# GPS.net
KiCad netlist of a schematic drawn in EAGLE
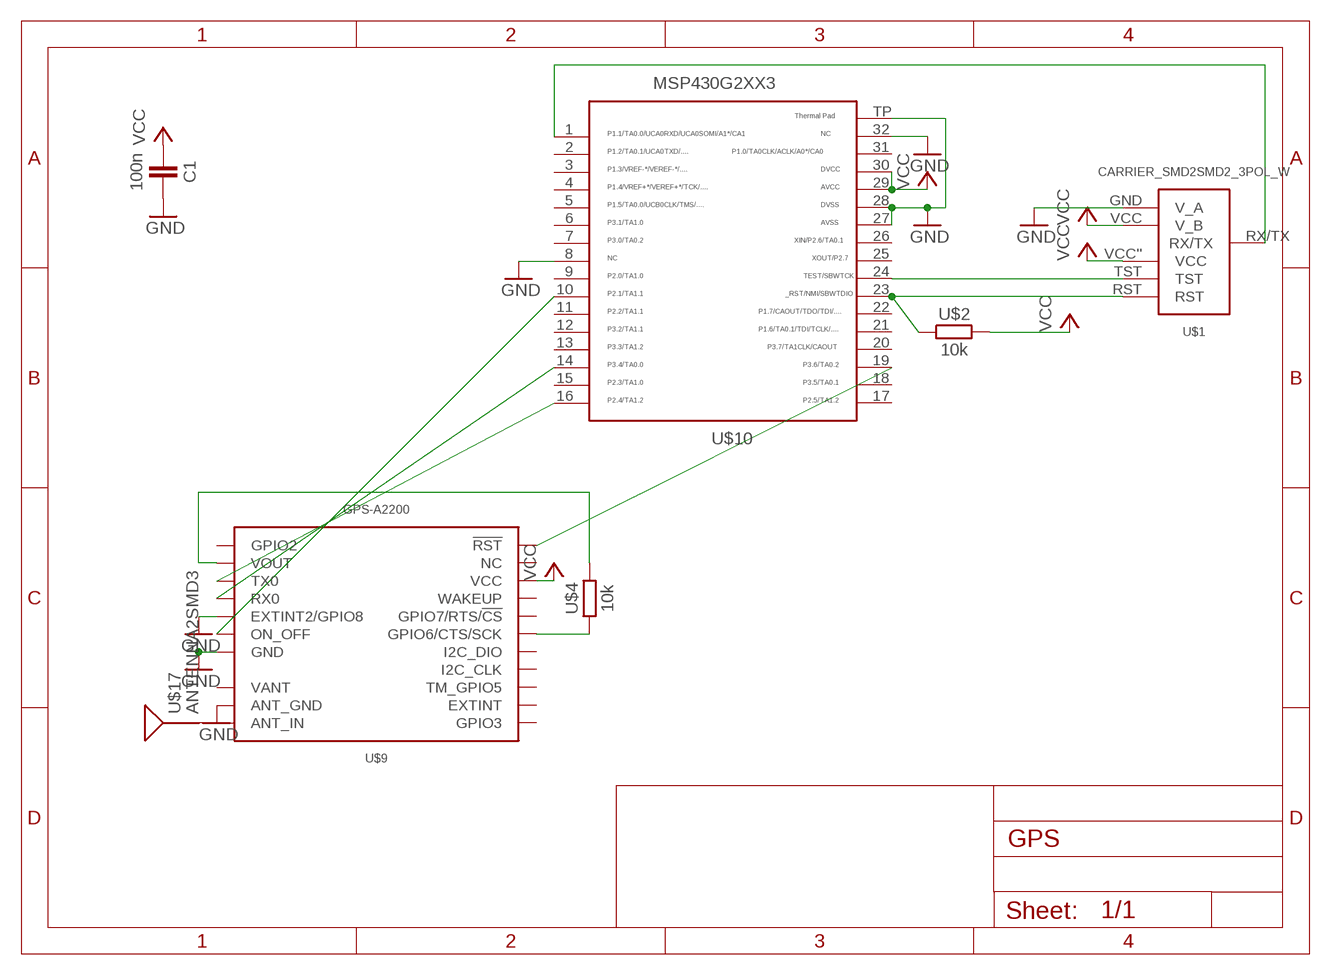
[diagram p0: schematic, sheet 1]

(export (version "E")
  (design (tool "Eeschema 10.0.6"))
  (components
    (comp (ref "C1")
      (value "100n")
      (footprint "eagle-import:603")
      (libsource (lib "eagle-import") (part "CAPACITOR"))
    )
    (comp (ref "U$1")
      (value "CARRIER_SMD2SMD2_3POL_W")
      (footprint "eagle-import:CARRIER_SMD2_WIDE_3POL")
      (libsource (lib "eagle-import") (part "CARRIER_SMD2SMD2_3POL_W"))
    )
    (comp (ref "U$2")
      (value "10k")
      (footprint "eagle-import:603")
      (libsource (lib "eagle-import") (part "RESISTOR0603"))
    )
    (comp (ref "U$4")
      (value "10k")
      (footprint "eagle-import:603")
      (libsource (lib "eagle-import") (part "RESISTOR0603"))
    )
    (comp (ref "U$9")
      (value "GPS-A2200")
      (footprint "eagle-import:A2200")
      (libsource (lib "eagle-import") (part "GPS-A2200"))
    )
    (comp (ref "U$10")
      (value "MSP430G2553")
      (footprint "eagle-import:QFN32")
      (libsource (lib "eagle-import") (part "MSP430G2553"))
    )
    (comp (ref "U$17")
      (value "ANTENNA2SMD3")
      (footprint "eagle-import:ANTENNA-CHIP4")
      (libsource (lib "eagle-import") (part "ANTENNA2SMD3"))
    )
  )
  (nets
    (net (code "1") (name "GND") (class "Default")
      (node (ref "C1") (pin "2") (pinfunction "2_2") (pintype "passive"))
      (node (ref "U$1") (pin "GND") (pinfunction "V_A_GND") (pintype "bidirectional"))
      (node (ref "U$10") (pin "27") (pinfunction "27_27") (pintype "bidirectional"))
      (node (ref "U$10") (pin "28") (pinfunction "28_28") (pintype "bidirectional"))
      (node (ref "U$10") (pin "32") (pinfunction "32_32") (pintype "bidirectional"))
      (node (ref "U$10") (pin "8") (pinfunction "8_8") (pintype "bidirectional"))
      (node (ref "U$10") (pin "TP") (pinfunction "TP_TP") (pintype "bidirectional"))
      (node (ref "U$9") (pin "ANT_GND") (pinfunction "ANT_GND_ANT_GND") (pintype "power_in"))
      (node (ref "U$9") (pin "EXTINT2/GPIO8") (pinfunction "EXTINT2/GPIO8_EXTINT2/GPIO8") (pintype "bidirectional"))
      (node (ref "U$9") (pin "GND@1") (pinfunction "GND_GND@1") (pintype "power_in"))
      (node (ref "U$9") (pin "GND@10") (pinfunction "GND_GND@10") (pintype "power_in"))
      (node (ref "U$9") (pin "GND@11") (pinfunction "GND_GND@11") (pintype "power_in"))
      (node (ref "U$9") (pin "GND@2") (pinfunction "GND_GND@2") (pintype "power_in"))
      (node (ref "U$9") (pin "GND@3") (pinfunction "GND_GND@3") (pintype "power_in"))
      (node (ref "U$9") (pin "GND@4") (pinfunction "GND_GND@4") (pintype "power_in"))
      (node (ref "U$9") (pin "GND@5") (pinfunction "GND_GND@5") (pintype "power_in"))
      (node (ref "U$9") (pin "GND@6") (pinfunction "GND_GND@6") (pintype "power_in"))
      (node (ref "U$9") (pin "GND@7") (pinfunction "GND_GND@7") (pintype "power_in"))
      (node (ref "U$9") (pin "GND@8") (pinfunction "GND_GND@8") (pintype "power_in"))
      (node (ref "U$9") (pin "GND@9") (pinfunction "GND_GND@9") (pintype "power_in"))
    )
    (net (code "2") (name "Net-(U$1-PadRST)") (class "Default")
      (node (ref "U$1") (pin "RST") (pinfunction "RST_RST") (pintype "bidirectional"))
      (node (ref "U$10") (pin "23") (pinfunction "23_23") (pintype "bidirectional"))
      (node (ref "U$2") (pin "1") (pinfunction "1_1") (pintype "passive"))
    )
    (net (code "3") (name "Net-(U$1-PadRX{slash}TX)") (class "Default")
      (node (ref "U$1") (pin "RX/TX") (pinfunction "RX/TX_RX/TX") (pintype "bidirectional"))
      (node (ref "U$10") (pin "1") (pinfunction "1_1") (pintype "bidirectional"))
    )
    (net (code "4") (name "Net-(U$1-PadTST)") (class "Default")
      (node (ref "U$1") (pin "TST") (pinfunction "TST_TST") (pintype "bidirectional"))
      (node (ref "U$10") (pin "24") (pinfunction "24_24") (pintype "bidirectional"))
    )
    (net (code "5") (name "Net-(U$4-Pad2)") (class "Default")
      (node (ref "U$4") (pin "2") (pinfunction "2_2") (pintype "passive"))
      (node (ref "U$9") (pin "VOUT") (pinfunction "VOUT_VOUT") (pintype "bidirectional"))
    )
    (net (code "6") (name "Net-(U$9-GPIO6{slash}CTS{slash}SCK)") (class "Default")
      (node (ref "U$4") (pin "1") (pinfunction "1_1") (pintype "passive"))
      (node (ref "U$9") (pin "GPIO6") (pinfunction "GPIO6/CTS/SCK_GPIO6") (pintype "input"))
    )
    (net (code "7") (name "Net-(U$9-~{RST})") (class "Default")
      (node (ref "U$10") (pin "19") (pinfunction "19_19") (pintype "bidirectional"))
      (node (ref "U$9") (pin "!RST") (pinfunction "~{RST}_!RST") (pintype "input"))
    )
    (net (code "8") (name "Net-(U$10-Pad10)") (class "Default")
      (node (ref "U$10") (pin "10") (pinfunction "10_10") (pintype "bidirectional"))
      (node (ref "U$9") (pin "ON_OFF") (pinfunction "ON_OFF_ON_OFF") (pintype "input"))
    )
    (net (code "9") (name "Net-(U$10-Pad14)") (class "Default")
      (node (ref "U$10") (pin "14") (pinfunction "14_14") (pintype "bidirectional"))
      (node (ref "U$9") (pin "RX0") (pinfunction "RX0_RX0") (pintype "input"))
    )
    (net (code "10") (name "Net-(U$10-Pad16)") (class "Default")
      (node (ref "U$10") (pin "16") (pinfunction "16_16") (pintype "bidirectional"))
      (node (ref "U$9") (pin "TX0") (pinfunction "TX0_TX0") (pintype "output"))
    )
    (net (code "11") (name "Net-(U$17-SIGNAL)") (class "Default")
      (node (ref "U$17") (pin "SIG") (pinfunction "SIGNAL_SIG") (pintype "bidirectional"))
      (node (ref "U$9") (pin "ANT_IN") (pinfunction "ANT_IN_ANT_IN") (pintype "bidirectional"))
    )
    (net (code "12") (name "VCC") (class "Default")
      (node (ref "C1") (pin "1") (pinfunction "1_1") (pintype "passive"))
      (node (ref "U$1") (pin "VCC") (pinfunction "V_B_VCC") (pintype "bidirectional"))
      (node (ref "U$1") (pin "VCC''") (pinfunction "VCC_VCC''") (pintype "bidirectional"))
      (node (ref "U$10") (pin "29") (pinfunction "29_29") (pintype "bidirectional"))
      (node (ref "U$10") (pin "30") (pinfunction "30_30") (pintype "bidirectional"))
      (node (ref "U$2") (pin "2") (pinfunction "2_2") (pintype "passive"))
      (node (ref "U$9") (pin "VCC") (pinfunction "VCC_VCC") (pintype "power_in"))
    )
    (net (code "13") (name "unconnected-(U$9-GPIO7{slash}RTS{slash}~{CS}-PadGPIO7)") (class "Default")
      (node (ref "U$9") (pin "GPIO7") (pinfunction "GPIO7/RTS/~{CS}_GPIO7") (pintype "input"))
    )
    (net (code "14") (name "unconnected-(U$9-PadEXTINT)") (class "Default")
      (node (ref "U$9") (pin "EXTINT") (pinfunction "EXTINT_EXTINT") (pintype "bidirectional"))
    )
    (net (code "15") (name "unconnected-(U$9-PadGPIO2)") (class "Default")
      (node (ref "U$9") (pin "GPIO2") (pinfunction "GPIO2_GPIO2") (pintype "bidirectional"))
    )
    (net (code "16") (name "unconnected-(U$9-PadGPIO3)") (class "Default")
      (node (ref "U$9") (pin "GPIO3") (pinfunction "GPIO3_GPIO3") (pintype "bidirectional"))
    )
    (net (code "17") (name "unconnected-(U$9-PadI2C_CLK)") (class "Default")
      (node (ref "U$9") (pin "I2C_CLK") (pinfunction "I2C_CLK_I2C_CLK") (pintype "open_collector"))
    )
    (net (code "18") (name "unconnected-(U$9-PadI2C_DIO)") (class "Default")
      (node (ref "U$9") (pin "I2C_DIO") (pinfunction "I2C_DIO_I2C_DIO") (pintype "open_collector"))
    )
    (net (code "19") (name "unconnected-(U$9-PadNC)") (class "Default")
      (node (ref "U$9") (pin "NC") (pinfunction "NC_NC") (pintype "no_connect"))
    )
    (net (code "20") (name "unconnected-(U$9-PadTM_GPIO5)") (class "Default")
      (node (ref "U$9") (pin "TM_GPIO5") (pinfunction "TM_GPIO5_TM_GPIO5") (pintype "output"))
    )
    (net (code "21") (name "unconnected-(U$9-PadVANT)") (class "Default")
      (node (ref "U$9") (pin "VANT") (pinfunction "VANT_VANT") (pintype "input"))
    )
    (net (code "22") (name "unconnected-(U$9-PadWAKEUP)") (class "Default")
      (node (ref "U$9") (pin "WAKEUP") (pinfunction "WAKEUP_WAKEUP") (pintype "output"))
    )
    (net (code "23") (name "unconnected-(U$10-Pad2)") (class "Default")
      (node (ref "U$10") (pin "2") (pinfunction "2_2") (pintype "bidirectional"))
    )
    (net (code "24") (name "unconnected-(U$10-Pad3)") (class "Default")
      (node (ref "U$10") (pin "3") (pinfunction "3_3") (pintype "bidirectional"))
    )
    (net (code "25") (name "unconnected-(U$10-Pad4)") (class "Default")
      (node (ref "U$10") (pin "4") (pinfunction "4_4") (pintype "bidirectional"))
    )
    (net (code "26") (name "unconnected-(U$10-Pad5)") (class "Default")
      (node (ref "U$10") (pin "5") (pinfunction "5_5") (pintype "bidirectional"))
    )
    (net (code "27") (name "unconnected-(U$10-Pad6)") (class "Default")
      (node (ref "U$10") (pin "6") (pinfunction "6_6") (pintype "bidirectional"))
    )
    (net (code "28") (name "unconnected-(U$10-Pad7)") (class "Default")
      (node (ref "U$10") (pin "7") (pinfunction "7_7") (pintype "bidirectional"))
    )
    (net (code "29") (name "unconnected-(U$10-Pad9)") (class "Default")
      (node (ref "U$10") (pin "9") (pinfunction "9_9") (pintype "bidirectional"))
    )
    (net (code "30") (name "unconnected-(U$10-Pad11)") (class "Default")
      (node (ref "U$10") (pin "11") (pinfunction "11_11") (pintype "bidirectional"))
    )
    (net (code "31") (name "unconnected-(U$10-Pad12)") (class "Default")
      (node (ref "U$10") (pin "12") (pinfunction "12_12") (pintype "bidirectional"))
    )
    (net (code "32") (name "unconnected-(U$10-Pad13)") (class "Default")
      (node (ref "U$10") (pin "13") (pinfunction "13_13") (pintype "bidirectional"))
    )
    (net (code "33") (name "unconnected-(U$10-Pad15)") (class "Default")
      (node (ref "U$10") (pin "15") (pinfunction "15_15") (pintype "bidirectional"))
    )
    (net (code "34") (name "unconnected-(U$10-Pad17)") (class "Default")
      (node (ref "U$10") (pin "17") (pinfunction "17_17") (pintype "bidirectional"))
    )
    (net (code "35") (name "unconnected-(U$10-Pad18)") (class "Default")
      (node (ref "U$10") (pin "18") (pinfunction "18_18") (pintype "bidirectional"))
    )
    (net (code "36") (name "unconnected-(U$10-Pad20)") (class "Default")
      (node (ref "U$10") (pin "20") (pinfunction "20_20") (pintype "bidirectional"))
    )
    (net (code "37") (name "unconnected-(U$10-Pad21)") (class "Default")
      (node (ref "U$10") (pin "21") (pinfunction "21_21") (pintype "bidirectional"))
    )
    (net (code "38") (name "unconnected-(U$10-Pad22)") (class "Default")
      (node (ref "U$10") (pin "22") (pinfunction "22_22") (pintype "bidirectional"))
    )
    (net (code "39") (name "unconnected-(U$10-Pad25)") (class "Default")
      (node (ref "U$10") (pin "25") (pinfunction "25_25") (pintype "bidirectional"))
    )
    (net (code "40") (name "unconnected-(U$10-Pad26)") (class "Default")
      (node (ref "U$10") (pin "26") (pinfunction "26_26") (pintype "bidirectional"))
    )
    (net (code "41") (name "unconnected-(U$10-Pad31)") (class "Default")
      (node (ref "U$10") (pin "31") (pinfunction "31_31") (pintype "bidirectional"))
    )
  )
)
